# 1-Schematic_PiHexaSub.net
KiCad netlist of a schematic drawn in EasyEDA
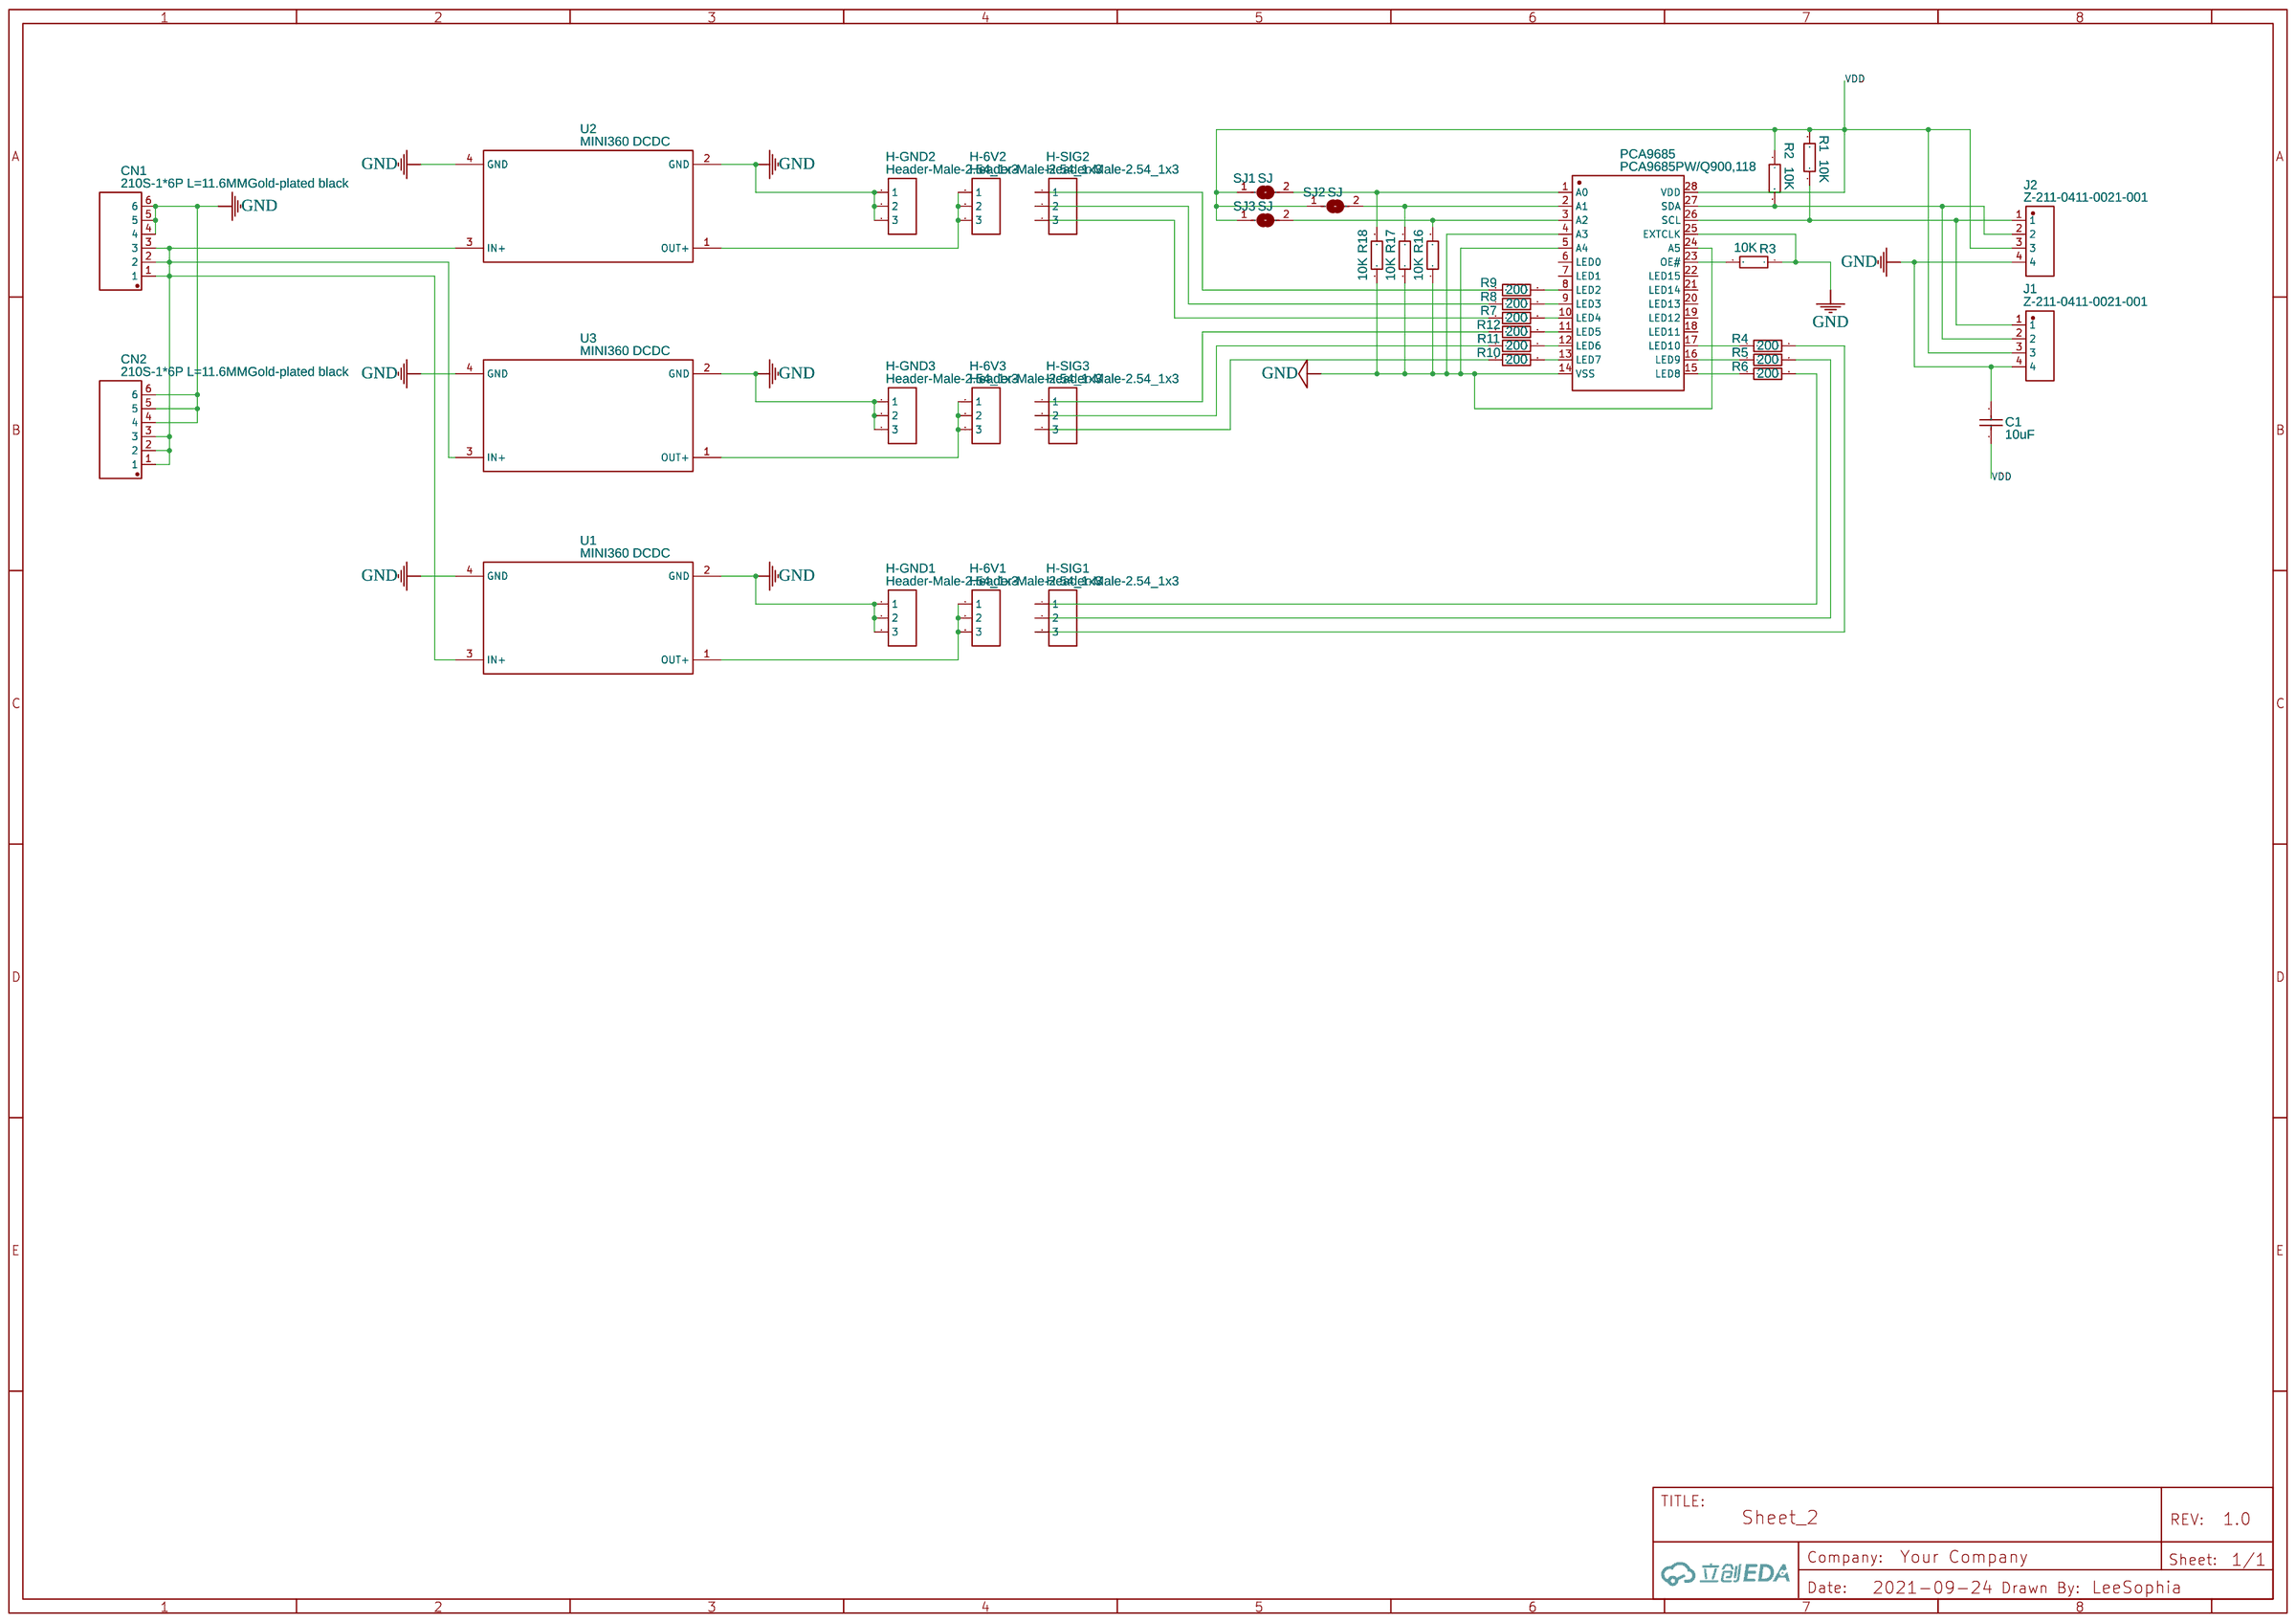
[diagram p0: schematic sheet]

(export (version "E")
  (design (tool "Eeschema 10.0.6"))
  (components
    (comp (ref "C1")
      (value "10uF")
      (fields
        (field (name "BOM_Manufacturer Part") "C2012X5R1E106KT000N")
        (field (name "BOM_Supplier Part") "C329933")
      )
      (libsource (lib "") (part "C2012X5R1E106KT000N"))
    )
    (comp (ref "CN1")
      (value "210S-1*6P L=11.6MMGold-plated black")
      (fields (field (name "BOM_Supplier Part") "C124380"))
      (libsource (lib "") (part "210S-1*6P L=11.6MMGold-plated black"))
    )
    (comp (ref "CN2")
      (value "210S-1*6P L=11.6MMGold-plated black")
      (fields (field (name "BOM_Supplier Part") "C124380"))
      (libsource (lib "") (part "210S-1*6P L=11.6MMGold-plated black"))
    )
    (comp (ref "H-6V1")
      (value "Header-Male-2.54_1x3")
      (fields
        (field (name "BOM_Manufacturer Part") "Header2.54mm 1*3P")
        (field (name "BOM_Supplier Part") "C49257")
      )
      (libsource (lib "") (part "Header-Male-2.54_1x3_1"))
    )
    (comp (ref "H-6V2")
      (value "Header-Male-2.54_1x3")
      (fields
        (field (name "BOM_Manufacturer Part") "Header2.54mm 1*3P")
        (field (name "BOM_Supplier Part") "C49257")
      )
      (libsource (lib "") (part "Header-Male-2.54_1x3_1"))
    )
    (comp (ref "H-6V3")
      (value "Header-Male-2.54_1x3")
      (fields
        (field (name "BOM_Manufacturer Part") "Header2.54mm 1*3P")
        (field (name "BOM_Supplier Part") "C49257")
      )
      (libsource (lib "") (part "Header-Male-2.54_1x3_1"))
    )
    (comp (ref "H-GND1")
      (value "Header-Male-2.54_1x3")
      (fields
        (field (name "BOM_Manufacturer Part") "Header2.54mm 1*3P")
        (field (name "BOM_Supplier Part") "C49257")
      )
      (libsource (lib "") (part "Header-Male-2.54_1x3_2"))
    )
    (comp (ref "H-GND2")
      (value "Header-Male-2.54_1x3")
      (fields
        (field (name "BOM_Manufacturer Part") "Header2.54mm 1*3P")
        (field (name "BOM_Supplier Part") "C49257")
      )
      (libsource (lib "") (part "Header-Male-2.54_1x3_2"))
    )
    (comp (ref "H-GND3")
      (value "Header-Male-2.54_1x3")
      (fields
        (field (name "BOM_Manufacturer Part") "Header2.54mm 1*3P")
        (field (name "BOM_Supplier Part") "C49257")
      )
      (libsource (lib "") (part "Header-Male-2.54_1x3_2"))
    )
    (comp (ref "H-SIG1")
      (value "Header-Male-2.54_1x3")
      (fields
        (field (name "BOM_Manufacturer Part") "Header2.54mm 1*3P")
        (field (name "BOM_Supplier Part") "C49257")
      )
      (libsource (lib "") (part "Header-Male-2.54_1x3"))
    )
    (comp (ref "H-SIG2")
      (value "Header-Male-2.54_1x3")
      (fields
        (field (name "BOM_Manufacturer Part") "Header2.54mm 1*3P")
        (field (name "BOM_Supplier Part") "C49257")
      )
      (libsource (lib "") (part "Header-Male-2.54_1x3"))
    )
    (comp (ref "H-SIG3")
      (value "Header-Male-2.54_1x3")
      (fields
        (field (name "BOM_Manufacturer Part") "Header2.54mm 1*3P")
        (field (name "BOM_Supplier Part") "C49257")
      )
      (libsource (lib "") (part "Header-Male-2.54_1x3"))
    )
    (comp (ref "J1")
      (value "Z-211-0411-0021-001")
      (fields (field (name "BOM_Supplier Part") "C152150"))
      (libsource (lib "") (part "Z-211-0411-0021-001"))
    )
    (comp (ref "J2")
      (value "Z-211-0411-0021-001")
      (fields (field (name "BOM_Supplier Part") "C152150"))
      (libsource (lib "") (part "Z-211-0411-0021-001"))
    )
    (comp (ref "PCA9685")
      (value "PCA9685PW/Q900,118")
      (fields (field (name "BOM_Supplier Part") "C92206"))
      (libsource (lib "") (part "PCA9685PW/Q900,118"))
    )
    (comp (ref "R1")
      (value "10K")
      (fields
        (field (name "BOM_Manufacturer Part") "RMCF0603JT10K0")
        (field (name "BOM_Supplier Part") "C238881")
      )
      (libsource (lib "") (part "RMCF0603JT10K0_1"))
    )
    (comp (ref "R2")
      (value "10K")
      (fields
        (field (name "BOM_Manufacturer Part") "RMCF0603JT10K0")
        (field (name "BOM_Supplier Part") "C238881")
      )
      (libsource (lib "") (part "RMCF0603JT10K0_1"))
    )
    (comp (ref "R3")
      (value "10K")
      (fields
        (field (name "BOM_Manufacturer Part") "RMCF0603JT10K0")
        (field (name "BOM_Supplier Part") "C238881")
      )
      (libsource (lib "") (part "RMCF0603JT10K0_2"))
    )
    (comp (ref "R4")
      (value "200")
      (fields
        (field (name "BOM_Manufacturer Part") "RMS06FT2000")
        (field (name "BOM_Supplier Part") "C209065")
      )
      (libsource (lib "") (part "RMS06FT2000"))
    )
    (comp (ref "R5")
      (value "200")
      (fields
        (field (name "BOM_Manufacturer Part") "RMS06FT2000")
        (field (name "BOM_Supplier Part") "C209065")
      )
      (libsource (lib "") (part "RMS06FT2000"))
    )
    (comp (ref "R6")
      (value "200")
      (fields
        (field (name "BOM_Manufacturer Part") "RMS06FT2000")
        (field (name "BOM_Supplier Part") "C209065")
      )
      (libsource (lib "") (part "RMS06FT2000"))
    )
    (comp (ref "R7")
      (value "200")
      (fields
        (field (name "BOM_Manufacturer Part") "RMS06FT2000")
        (field (name "BOM_Supplier Part") "C209065")
      )
      (libsource (lib "") (part "RMS06FT2000"))
    )
    (comp (ref "R8")
      (value "200")
      (fields
        (field (name "BOM_Manufacturer Part") "RMS06FT2000")
        (field (name "BOM_Supplier Part") "C209065")
      )
      (libsource (lib "") (part "RMS06FT2000"))
    )
    (comp (ref "R9")
      (value "200")
      (fields
        (field (name "BOM_Manufacturer Part") "RMS06FT2000")
        (field (name "BOM_Supplier Part") "C209065")
      )
      (libsource (lib "") (part "RMS06FT2000"))
    )
    (comp (ref "R10")
      (value "200")
      (fields
        (field (name "BOM_Manufacturer Part") "RMS06FT2000")
        (field (name "BOM_Supplier Part") "C209065")
      )
      (libsource (lib "") (part "RMS06FT2000"))
    )
    (comp (ref "R11")
      (value "200")
      (fields
        (field (name "BOM_Manufacturer Part") "RMS06FT2000")
        (field (name "BOM_Supplier Part") "C209065")
      )
      (libsource (lib "") (part "RMS06FT2000"))
    )
    (comp (ref "R12")
      (value "200")
      (fields
        (field (name "BOM_Manufacturer Part") "RMS06FT2000")
        (field (name "BOM_Supplier Part") "C209065")
      )
      (libsource (lib "") (part "RMS06FT2000"))
    )
    (comp (ref "R16")
      (value "10K")
      (fields
        (field (name "BOM_Manufacturer Part") "RMCF0603JT10K0")
        (field (name "BOM_Supplier Part") "C238881")
      )
      (libsource (lib "") (part "RMCF0603JT10K0"))
    )
    (comp (ref "R17")
      (value "10K")
      (fields
        (field (name "BOM_Manufacturer Part") "RMCF0603JT10K0")
        (field (name "BOM_Supplier Part") "C238881")
      )
      (libsource (lib "") (part "RMCF0603JT10K0"))
    )
    (comp (ref "R18")
      (value "10K")
      (fields
        (field (name "BOM_Manufacturer Part") "RMCF0603JT10K0")
        (field (name "BOM_Supplier Part") "C238881")
      )
      (libsource (lib "") (part "RMCF0603JT10K0"))
    )
    (comp (ref "SJ1") (value "SJ") (libsource (lib "") (part "SJ")))
    (comp (ref "SJ2") (value "SJ") (libsource (lib "") (part "SJ")))
    (comp (ref "SJ3") (value "SJ") (libsource (lib "") (part "SJ")))
    (comp (ref "U1") (value "MINI360 DCDC") (libsource (lib "") (part "MINI360 DCDC")))
    (comp (ref "U2") (value "MINI360 DCDC") (libsource (lib "") (part "MINI360 DCDC")))
    (comp (ref "U3") (value "MINI360 DCDC") (libsource (lib "") (part "MINI360 DCDC")))
  )
  (nets
    (net (code "1") (name "/VDD") (class "Default")
      (node (ref "C1") (pin "2") (pinfunction "2_2") (pintype "input"))
      (node (ref "J1") (pin "3") (pinfunction "3_3") (pintype "unspecified"))
      (node (ref "J2") (pin "3") (pinfunction "3_3") (pintype "unspecified"))
      (node (ref "PCA9685") (pin "28") (pinfunction "VDD_28") (pintype "unspecified"))
      (node (ref "R1") (pin "1") (pinfunction "1_1") (pintype "unspecified"))
      (node (ref "R2") (pin "1") (pinfunction "1_1") (pintype "unspecified"))
      (node (ref "SJ1") (pin "1") (pinfunction "1_1") (pintype "bidirectional"))
      (node (ref "SJ2") (pin "1") (pinfunction "1_1") (pintype "bidirectional"))
      (node (ref "SJ3") (pin "1") (pinfunction "1_1") (pintype "bidirectional"))
    )
    (net (code "2") (name "GND") (class "Default")
      (node (ref "C1") (pin "1") (pinfunction "1_1") (pintype "input"))
      (node (ref "CN1") (pin "4") (pinfunction "4_4") (pintype "unspecified"))
      (node (ref "CN1") (pin "5") (pinfunction "5_5") (pintype "unspecified"))
      (node (ref "CN1") (pin "6") (pinfunction "6_6") (pintype "unspecified"))
      (node (ref "CN2") (pin "4") (pinfunction "4_4") (pintype "unspecified"))
      (node (ref "CN2") (pin "5") (pinfunction "5_5") (pintype "unspecified"))
      (node (ref "CN2") (pin "6") (pinfunction "6_6") (pintype "unspecified"))
      (node (ref "H-GND1") (pin "1") (pinfunction "1_1") (pintype "input"))
      (node (ref "H-GND1") (pin "2") (pinfunction "2_2") (pintype "input"))
      (node (ref "H-GND1") (pin "3") (pinfunction "3_3") (pintype "input"))
      (node (ref "H-GND2") (pin "1") (pinfunction "1_1") (pintype "input"))
      (node (ref "H-GND2") (pin "2") (pinfunction "2_2") (pintype "input"))
      (node (ref "H-GND2") (pin "3") (pinfunction "3_3") (pintype "input"))
      (node (ref "H-GND3") (pin "1") (pinfunction "1_1") (pintype "input"))
      (node (ref "H-GND3") (pin "2") (pinfunction "2_2") (pintype "input"))
      (node (ref "H-GND3") (pin "3") (pinfunction "3_3") (pintype "input"))
      (node (ref "J1") (pin "4") (pinfunction "4_4") (pintype "unspecified"))
      (node (ref "J2") (pin "4") (pinfunction "4_4") (pintype "unspecified"))
      (node (ref "PCA9685") (pin "14") (pinfunction "VSS_14") (pintype "unspecified"))
      (node (ref "PCA9685") (pin "24") (pinfunction "A5_24") (pintype "unspecified"))
      (node (ref "PCA9685") (pin "25") (pinfunction "EXTCLK_25") (pintype "unspecified"))
      (node (ref "PCA9685") (pin "4") (pinfunction "A3_4") (pintype "unspecified"))
      (node (ref "PCA9685") (pin "5") (pinfunction "A4_5") (pintype "unspecified"))
      (node (ref "R16") (pin "1") (pinfunction "1_1") (pintype "unspecified"))
      (node (ref "R17") (pin "1") (pinfunction "1_1") (pintype "unspecified"))
      (node (ref "R18") (pin "1") (pinfunction "1_1") (pintype "unspecified"))
      (node (ref "R3") (pin "1") (pinfunction "1_1") (pintype "unspecified"))
      (node (ref "U1") (pin "2") (pinfunction "GND_2") (pintype "unspecified"))
      (node (ref "U1") (pin "4") (pinfunction "GND_4") (pintype "unspecified"))
      (node (ref "U2") (pin "2") (pinfunction "GND_2") (pintype "unspecified"))
      (node (ref "U2") (pin "4") (pinfunction "GND_4") (pintype "unspecified"))
      (node (ref "U3") (pin "2") (pinfunction "GND_2") (pintype "unspecified"))
      (node (ref "U3") (pin "4") (pinfunction "GND_4") (pintype "unspecified"))
    )
    (net (code "3") (name "Net-(H-SIG1-Pad1)") (class "Default")
      (node (ref "H-SIG1") (pin "1") (pinfunction "1_1") (pintype "input"))
      (node (ref "R6") (pin "2") (pinfunction "2_2") (pintype "unspecified"))
    )
    (net (code "4") (name "Net-(H-SIG1-Pad2)") (class "Default")
      (node (ref "H-SIG1") (pin "2") (pinfunction "2_2") (pintype "input"))
      (node (ref "R5") (pin "2") (pinfunction "2_2") (pintype "unspecified"))
    )
    (net (code "5") (name "Net-(H-SIG1-Pad3)") (class "Default")
      (node (ref "H-SIG1") (pin "3") (pinfunction "3_3") (pintype "input"))
      (node (ref "R4") (pin "2") (pinfunction "2_2") (pintype "unspecified"))
    )
    (net (code "6") (name "Net-(H-SIG2-Pad1)") (class "Default")
      (node (ref "H-SIG2") (pin "1") (pinfunction "1_1") (pintype "input"))
      (node (ref "R9") (pin "1") (pinfunction "1_1") (pintype "unspecified"))
    )
    (net (code "7") (name "Net-(H-SIG2-Pad2)") (class "Default")
      (node (ref "H-SIG2") (pin "2") (pinfunction "2_2") (pintype "input"))
      (node (ref "R8") (pin "1") (pinfunction "1_1") (pintype "unspecified"))
    )
    (net (code "8") (name "Net-(H-SIG2-Pad3)") (class "Default")
      (node (ref "H-SIG2") (pin "3") (pinfunction "3_3") (pintype "input"))
      (node (ref "R7") (pin "1") (pinfunction "1_1") (pintype "unspecified"))
    )
    (net (code "9") (name "Net-(H-SIG3-Pad1)") (class "Default")
      (node (ref "H-SIG3") (pin "1") (pinfunction "1_1") (pintype "input"))
      (node (ref "R12") (pin "1") (pinfunction "1_1") (pintype "unspecified"))
    )
    (net (code "10") (name "Net-(H-SIG3-Pad2)") (class "Default")
      (node (ref "H-SIG3") (pin "2") (pinfunction "2_2") (pintype "input"))
      (node (ref "R11") (pin "1") (pinfunction "1_1") (pintype "unspecified"))
    )
    (net (code "11") (name "Net-(H-SIG3-Pad3)") (class "Default")
      (node (ref "H-SIG3") (pin "3") (pinfunction "3_3") (pintype "input"))
      (node (ref "R10") (pin "1") (pinfunction "1_1") (pintype "unspecified"))
    )
    (net (code "12") (name "Net-(PCA9685-A0)") (class "Default")
      (node (ref "PCA9685") (pin "1") (pinfunction "A0_1") (pintype "unspecified"))
      (node (ref "R18") (pin "2") (pinfunction "2_2") (pintype "unspecified"))
      (node (ref "SJ1") (pin "2") (pinfunction "2_2") (pintype "bidirectional"))
    )
    (net (code "13") (name "Net-(PCA9685-A1)") (class "Default")
      (node (ref "PCA9685") (pin "2") (pinfunction "A1_2") (pintype "unspecified"))
      (node (ref "R17") (pin "2") (pinfunction "2_2") (pintype "unspecified"))
      (node (ref "SJ2") (pin "2") (pinfunction "2_2") (pintype "bidirectional"))
    )
    (net (code "14") (name "Net-(PCA9685-A2)") (class "Default")
      (node (ref "PCA9685") (pin "3") (pinfunction "A2_3") (pintype "unspecified"))
      (node (ref "R16") (pin "2") (pinfunction "2_2") (pintype "unspecified"))
      (node (ref "SJ3") (pin "2") (pinfunction "2_2") (pintype "bidirectional"))
    )
    (net (code "15") (name "Net-(PCA9685-LED2)") (class "Default")
      (node (ref "PCA9685") (pin "8") (pinfunction "LED2_8") (pintype "unspecified"))
      (node (ref "R9") (pin "2") (pinfunction "2_2") (pintype "unspecified"))
    )
    (net (code "16") (name "Net-(PCA9685-LED3)") (class "Default")
      (node (ref "PCA9685") (pin "9") (pinfunction "LED3_9") (pintype "unspecified"))
      (node (ref "R8") (pin "2") (pinfunction "2_2") (pintype "unspecified"))
    )
    (net (code "17") (name "Net-(PCA9685-LED4)") (class "Default")
      (node (ref "PCA9685") (pin "10") (pinfunction "LED4_10") (pintype "unspecified"))
      (node (ref "R7") (pin "2") (pinfunction "2_2") (pintype "unspecified"))
    )
    (net (code "18") (name "Net-(PCA9685-LED5)") (class "Default")
      (node (ref "PCA9685") (pin "11") (pinfunction "LED5_11") (pintype "unspecified"))
      (node (ref "R12") (pin "2") (pinfunction "2_2") (pintype "unspecified"))
    )
    (net (code "19") (name "Net-(PCA9685-LED6)") (class "Default")
      (node (ref "PCA9685") (pin "12") (pinfunction "LED6_12") (pintype "unspecified"))
      (node (ref "R11") (pin "2") (pinfunction "2_2") (pintype "unspecified"))
    )
    (net (code "20") (name "Net-(PCA9685-LED7)") (class "Default")
      (node (ref "PCA9685") (pin "13") (pinfunction "LED7_13") (pintype "unspecified"))
      (node (ref "R10") (pin "2") (pinfunction "2_2") (pintype "unspecified"))
    )
    (net (code "21") (name "Net-(PCA9685-LED8)") (class "Default")
      (node (ref "PCA9685") (pin "15") (pinfunction "LED8_15") (pintype "unspecified"))
      (node (ref "R6") (pin "1") (pinfunction "1_1") (pintype "unspecified"))
    )
    (net (code "22") (name "Net-(PCA9685-LED9)") (class "Default")
      (node (ref "PCA9685") (pin "16") (pinfunction "LED9_16") (pintype "unspecified"))
      (node (ref "R5") (pin "1") (pinfunction "1_1") (pintype "unspecified"))
    )
    (net (code "23") (name "Net-(PCA9685-LED10)") (class "Default")
      (node (ref "PCA9685") (pin "17") (pinfunction "LED10_17") (pintype "unspecified"))
      (node (ref "R4") (pin "1") (pinfunction "1_1") (pintype "unspecified"))
    )
    (net (code "24") (name "Net-(PCA9685-OE#)") (class "Default")
      (node (ref "PCA9685") (pin "23") (pinfunction "OE#_23") (pintype "unspecified"))
      (node (ref "R3") (pin "2") (pinfunction "2_2") (pintype "unspecified"))
    )
    (net (code "25") (name "Net-(PCA9685-SCL)") (class "Default")
      (node (ref "J1") (pin "1") (pinfunction "1_1") (pintype "unspecified"))
      (node (ref "J2") (pin "1") (pinfunction "1_1") (pintype "unspecified"))
      (node (ref "PCA9685") (pin "26") (pinfunction "SCL_26") (pintype "unspecified"))
      (node (ref "R1") (pin "2") (pinfunction "2_2") (pintype "unspecified"))
    )
    (net (code "26") (name "Net-(PCA9685-SDA)") (class "Default")
      (node (ref "J1") (pin "2") (pinfunction "2_2") (pintype "unspecified"))
      (node (ref "J2") (pin "2") (pinfunction "2_2") (pintype "unspecified"))
      (node (ref "PCA9685") (pin "27") (pinfunction "SDA_27") (pintype "unspecified"))
      (node (ref "R2") (pin "2") (pinfunction "2_2") (pintype "unspecified"))
    )
    (net (code "27") (name "Net-(U1-IN+)") (class "Default")
      (node (ref "CN1") (pin "1") (pinfunction "1_1") (pintype "unspecified"))
      (node (ref "CN1") (pin "2") (pinfunction "2_2") (pintype "unspecified"))
      (node (ref "CN1") (pin "3") (pinfunction "3_3") (pintype "unspecified"))
      (node (ref "CN2") (pin "1") (pinfunction "1_1") (pintype "unspecified"))
      (node (ref "CN2") (pin "2") (pinfunction "2_2") (pintype "unspecified"))
      (node (ref "CN2") (pin "3") (pinfunction "3_3") (pintype "unspecified"))
      (node (ref "U1") (pin "3") (pinfunction "IN+_3") (pintype "unspecified"))
      (node (ref "U2") (pin "3") (pinfunction "IN+_3") (pintype "unspecified"))
      (node (ref "U3") (pin "3") (pinfunction "IN+_3") (pintype "unspecified"))
    )
    (net (code "28") (name "Net-(U1-OUT+)") (class "Default")
      (node (ref "H-6V1") (pin "1") (pinfunction "1_1") (pintype "input"))
      (node (ref "H-6V1") (pin "2") (pinfunction "2_2") (pintype "input"))
      (node (ref "H-6V1") (pin "3") (pinfunction "3_3") (pintype "input"))
      (node (ref "U1") (pin "1") (pinfunction "OUT+_1") (pintype "unspecified"))
    )
    (net (code "29") (name "Net-(U2-OUT+)") (class "Default")
      (node (ref "H-6V2") (pin "1") (pinfunction "1_1") (pintype "input"))
      (node (ref "H-6V2") (pin "2") (pinfunction "2_2") (pintype "input"))
      (node (ref "H-6V2") (pin "3") (pinfunction "3_3") (pintype "input"))
      (node (ref "U2") (pin "1") (pinfunction "OUT+_1") (pintype "unspecified"))
    )
    (net (code "30") (name "Net-(U3-OUT+)") (class "Default")
      (node (ref "H-6V3") (pin "1") (pinfunction "1_1") (pintype "input"))
      (node (ref "H-6V3") (pin "2") (pinfunction "2_2") (pintype "input"))
      (node (ref "H-6V3") (pin "3") (pinfunction "3_3") (pintype "input"))
      (node (ref "U3") (pin "1") (pinfunction "OUT+_1") (pintype "unspecified"))
    )
    (net (code "31") (name "unconnected-(PCA9685-LED0-Pad6)") (class "Default")
      (node (ref "PCA9685") (pin "6") (pinfunction "LED0_6") (pintype "unspecified"))
    )
    (net (code "32") (name "unconnected-(PCA9685-LED1-Pad7)") (class "Default")
      (node (ref "PCA9685") (pin "7") (pinfunction "LED1_7") (pintype "unspecified"))
    )
    (net (code "33") (name "unconnected-(PCA9685-LED11-Pad18)") (class "Default")
      (node (ref "PCA9685") (pin "18") (pinfunction "LED11_18") (pintype "unspecified"))
    )
    (net (code "34") (name "unconnected-(PCA9685-LED12-Pad19)") (class "Default")
      (node (ref "PCA9685") (pin "19") (pinfunction "LED12_19") (pintype "unspecified"))
    )
    (net (code "35") (name "unconnected-(PCA9685-LED13-Pad20)") (class "Default")
      (node (ref "PCA9685") (pin "20") (pinfunction "LED13_20") (pintype "unspecified"))
    )
    (net (code "36") (name "unconnected-(PCA9685-LED14-Pad21)") (class "Default")
      (node (ref "PCA9685") (pin "21") (pinfunction "LED14_21") (pintype "unspecified"))
    )
    (net (code "37") (name "unconnected-(PCA9685-LED15-Pad22)") (class "Default")
      (node (ref "PCA9685") (pin "22") (pinfunction "LED15_22") (pintype "unspecified"))
    )
  )
)
